# Sheet1.net
KiCad netlist of a schematic drawn in Altium Designer
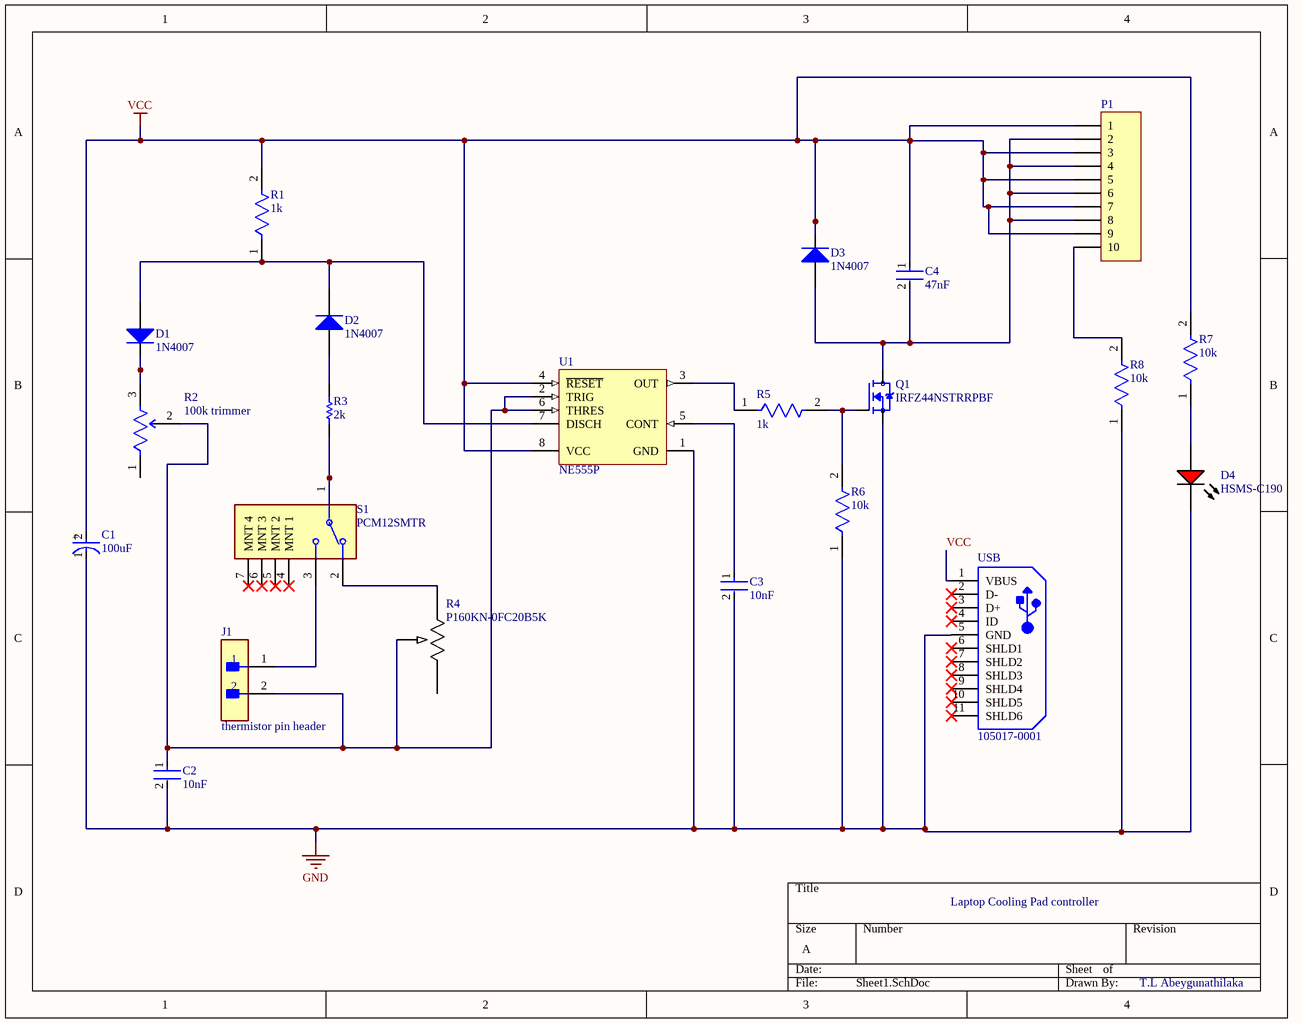
[diagram p0: Sheet1.SchDoc]

(export (version "E")
  (design (tool "Eeschema 10.0.6"))
  (components
    (comp (ref "C1")
      (value "100uF")
      (footprint "FP-TAJW-MFG")
      (description "100uF 4V  ±10% 400mΩ 2312  SMD Tantalum Capacitor")
      (fields (field (name "TOLERANCE") "10%"))
      (libsource (lib "Altium Content Vault") (part "a00bbbee19879c290e62620ae7e47b1"))
    )
    (comp (ref "C2")
      (value "10nF")
      (footprint "FP-0805-L_2_01_0_2-W_1_25-IPC_B")
      (description "General Purpose Ceramic Capacitor, 0805, 10nF, 5%, X7R, 0.15, 50V")
      (fields (field (name "VOLTAGE") "50V") (field (name "TOLERANCE") "5%"))
      (libsource (lib "Altium Content Vault") (part "02cd4be3c70576c341d710602a673aa"))
    )
    (comp (ref "C3")
      (value "10nF")
      (footprint "FP-0805-L_2_01_0_2-W_1_25-IPC_B")
      (description "General Purpose Ceramic Capacitor, 0805, 10nF, 5%, X7R, 0.15, 50V")
      (fields (field (name "VOLTAGE") "50V") (field (name "TOLERANCE") "5%"))
      (libsource (lib "Altium Content Vault") (part "02cd4be3c70576c341d710602a673aa"))
    )
    (comp (ref "C4")
      (value "47nF")
      (footprint "FP-VY2472M49Y5UG63V7-MFG")
      (description "Capacitor Ceramic 4700pF ±20% Y5U BULK RADIAL")
      (fields (field (name "TOLERANCE") "20%"))
      (libsource (lib "Altium Content Vault") (part "02cd4be3c70576c341d710602a673aa"))
    )
    (comp (ref "D1")
      (value "1N4007")
      (footprint "My_DO41")
      (description "1 Amp Diode")
      (fields (field (name "ASID PART NUMBER") "1n4007-AS"))
      (libsource (lib "Mylib+Rev+4") (part "1N4007"))
    )
    (comp (ref "D2")
      (value "1N4007")
      (footprint "My_DO41")
      (description "1 Amp Diode")
      (fields (field (name "ASID PART NUMBER") "1n4007-AS"))
      (libsource (lib "Mylib+Rev+4") (part "1N4007"))
    )
    (comp (ref "D3")
      (value "1N4007")
      (footprint "My_DO41")
      (description "1 Amp Diode")
      (fields (field (name "ASID PART NUMBER") "1n4007-AS"))
      (libsource (lib "Mylib+Rev+4") (part "1N4007"))
    )
    (comp (ref "D4")
      (value "HSMS-C190")
      (footprint "AVAG-HSMX-C190_V")
      (description "LED Uni-Color Red, 52 mW, 20 mA, -40 to 85 degC, 2-Pin SMD, RoHS, Tape and Reel")
      (fields (field (name "MANUFACTURER") "Avago"))
      (libsource (lib "Altium Content Vault") (part "LED-RED-AK-2"))
    )
    (comp (ref "J1")
      (value "thermistor pin header")
      (footprint "FP-M22-2510205-MFG")
      (description "CONN HEADER VERT 2POS 2MM")
      (fields
        (field (name "MANUFACTURER") "Harwin")
        (field (name "OCTOPART") "https://octopart.com/m22-2510205-harwin-2538221")
      )
      (libsource (lib "Altium Content Vault") (part "3bc925449376181038e59eaffc5286c"))
    )
    (comp (ref "P1")
      (value "Header 10")
      (footprint "MY_MA10-1")
      (description "Header, 10-Pin")
      (fields (field (name "ASID PART NUMBER") "Header 10-AS"))
      (libsource (lib "Mylib+Rev+4") (part "Header 10"))
    )
    (comp (ref "Q1")
      (value "IRFZ44NSTRRPBF")
      (footprint "DPAK254P1524X483-3N")
      (fields (field (name "MF") "Infineon Technologies"))
      (libsource (lib "IRFZ44NSTRRPBF") (part "IRFZ44NSTRRPBF"))
    )
    (comp (ref "R1")
      (value "1k")
      (footprint "FP-RP732B-MFG")
      (description "Res Thin Film 1206 1.0KΩ 0.1% 0.25W 15ppm/°C Molded SMD")
      (fields
        (field (name "OCTOPART") "https://octopart.com/rp73d2b1k0btg-te+connectivity-42012461")
        (field (name "MANUFACTURER") "TE Connectivity")
      )
      (libsource (lib "Altium Content Vault") (part "1029c3af85768c4190bb7ad29bc67b5"))
    )
    (comp (ref "R2")
      (value "100k trimmer")
      (footprint "FP-3296W-MFG")
      (description "TRIMMER 50K OHM 0.5W PC PIN TOP")
      (fields (field (name "TOLERANCE") "10%"))
      (libsource (lib "Altium Content Vault") (part "2dcfd2547301a7d3209a5e99acfd772"))
    )
    (comp (ref "R3")
      (value "2k")
      (footprint "RESC2013X60X35LL10T20")
      (fields (field (name "PART NUMBER") "RT0805FRE072KL") (field (name "MANUFACTURER") "Yageo"))
      (libsource (lib "Altium Content Vault") (part "RES"))
    )
    (comp (ref "R4")
      (value "P160KN-0FC20B5K")
      (footprint "POT_P160KN_F20_TTE")
      (description "No Description Available")
      (libsource (lib "P160KN-0FC20B5K") (part "P160KN-0FC20B5K"))
    )
    (comp (ref "R5")
      (value "1k")
      (footprint "FP-RC2012-MFG")
      (description "Res Thick Film 0805 1kΩ 1% 0.125W ±100ppm/°C Molded SMD T/R")
      (fields (field (name "TOLERANCE") "1%"))
      (libsource (lib "Altium Content Vault") (part "1029c3af85768c4190bb7ad29bc67b5"))
    )
    (comp (ref "R6")
      (value "10k")
      (footprint "FP-RMCF0805-IPC_A")
      (description "10kΩ ±5% 0.125W 0805 Thick Film Chip Resistor AEC-Q200 compliant")
      (fields (field (name "TOLERANCE") "5%"))
      (libsource (lib "Altium Content Vault") (part "1029c3af85768c4190bb7ad29bc67b5"))
    )
    (comp (ref "R7")
      (value "10k")
      (footprint "FP-RMCF0805-IPC_A")
      (description "10kΩ ±5% 0.125W 0805 Thick Film Chip Resistor AEC-Q200 compliant")
      (fields (field (name "TOLERANCE") "5%"))
      (libsource (lib "Altium Content Vault") (part "1029c3af85768c4190bb7ad29bc67b5"))
    )
    (comp (ref "R8")
      (value "10k")
      (footprint "FP-RMCF0805-IPC_A")
      (description "10kΩ ±5% 0.125W 0805 Thick Film Chip Resistor AEC-Q200 compliant")
      (fields (field (name "TOLERANCE") "5%"))
      (libsource (lib "Altium Content Vault") (part "1029c3af85768c4190bb7ad29bc67b5"))
    )
    (comp (ref "S1")
      (value "PCM12SMTR")
      (footprint "FP-PCM12SMTR-MFG")
      (description "SWITCH SLIDE SPDT 300MA 6V")
      (libsource (lib "Altium Content Vault") (part "1a3f67d7e2b5469b171eeab59ffb4d2"))
    )
    (comp (ref "U1")
      (value "NE555P")
      (footprint "P0008A")
      (description "Precision Timer, 4.5 to 16 V, 0 to 70 degC, 8-Pin DIP, Pb-Free, Tube")
      (fields (field (name "MANUFACTURER") "TexasInstruments"))
      (libsource (lib "Altium Content Vault") (part "TI-NE555-P8"))
    )
    (comp (ref "USB")
      (value "105017-0001")
      (footprint "USB-MICRO-B_V")
      (fields (field (name "MANUFACTURER") "Molex"))
      (libsource (lib "Altium Content Vault") (part "USB-5-6SHLD"))
    )
  )
  (nets
    (net (code "1") (name "GND") (class "Default")
      (node (ref "C1") (pin "1") (pinfunction "C_1") (pintype "passive"))
      (node (ref "C2") (pin "2") (pinfunction "2_2") (pintype "passive"))
      (node (ref "C3") (pin "2") (pinfunction "2_2") (pintype "passive"))
      (node (ref "D4") (pin "2") (pinfunction "K_2") (pintype "passive"))
      (node (ref "Q1") (pin "3") (pinfunction "S_3") (pintype "passive"))
      (node (ref "R6") (pin "1") (pinfunction "1_1") (pintype "passive"))
      (node (ref "R8") (pin "1") (pinfunction "1_1") (pintype "passive"))
      (node (ref "U1") (pin "1") (pinfunction "GND_1") (pintype "power_in"))
      (node (ref "USB") (pin "5") (pinfunction "GND_5") (pintype "passive"))
    )
    (net (code "2") (name "Net-(D2-PadA)") (class "Default")
      (node (ref "D2") (pin "A") (pinfunction "A_A") (pintype "passive"))
      (node (ref "R3") (pin "2") (pinfunction "2_2") (pintype "passive"))
    )
    (net (code "3") (name "Net-(D4-A)") (class "Default")
      (node (ref "D4") (pin "1") (pinfunction "A_1") (pintype "passive"))
      (node (ref "R7") (pin "1") (pinfunction "1_1") (pintype "passive"))
    )
    (net (code "4") (name "Net-(J1-Pad1)") (class "Default")
      (node (ref "J1") (pin "1") (pinfunction "1_1") (pintype "passive"))
      (node (ref "S1") (pin "3") (pinfunction "3_3") (pintype "passive"))
    )
    (net (code "5") (name "Net-(P1-Pad10)") (class "Default")
      (node (ref "P1") (pin "10") (pinfunction "10_10") (pintype "passive"))
      (node (ref "R8") (pin "2") (pinfunction "2_2") (pintype "passive"))
    )
    (net (code "6") (name "Net-(Q1-D)") (class "Default")
      (node (ref "C4") (pin "2") (pinfunction "2_2") (pintype "passive"))
      (node (ref "D3") (pin "A") (pinfunction "A_A") (pintype "passive"))
      (node (ref "P1") (pin "2") (pinfunction "2_2") (pintype "passive"))
      (node (ref "P1") (pin "4") (pinfunction "4_4") (pintype "passive"))
      (node (ref "P1") (pin "6") (pinfunction "6_6") (pintype "passive"))
      (node (ref "P1") (pin "8") (pinfunction "8_8") (pintype "passive"))
      (node (ref "Q1") (pin "2") (pinfunction "D_2") (pintype "passive"))
    )
    (net (code "7") (name "Net-(Q1-G)") (class "Default")
      (node (ref "Q1") (pin "1") (pinfunction "G_1") (pintype "passive"))
      (node (ref "R5") (pin "2") (pinfunction "2_2") (pintype "passive"))
      (node (ref "R6") (pin "2") (pinfunction "2_2") (pintype "passive"))
    )
    (net (code "8") (name "Net-(R2-CW)") (class "Default")
      (node (ref "D1") (pin "K") (pinfunction "K_K") (pintype "passive"))
      (node (ref "R2") (pin "3") (pinfunction "CW_3") (pintype "passive"))
    )
    (net (code "9") (name "Net-(R2-WIPER)") (class "Default")
      (node (ref "C2") (pin "1") (pinfunction "1_1") (pintype "passive"))
      (node (ref "J1") (pin "2") (pinfunction "2_2") (pintype "passive"))
      (node (ref "R2") (pin "2") (pinfunction "WIPER_2") (pintype "passive"))
      (node (ref "R4") (pin "2") (pinfunction "2_2") (pintype "passive"))
      (node (ref "U1") (pin "2") (pinfunction "TRIG_2") (pintype "input"))
      (node (ref "U1") (pin "6") (pinfunction "THRES_6") (pintype "input"))
    )
    (net (code "10") (name "Net-(R3-Pad1)") (class "Default")
      (node (ref "R3") (pin "1") (pinfunction "1_1") (pintype "passive"))
      (node (ref "S1") (pin "1") (pinfunction "1_1") (pintype "passive"))
    )
    (net (code "11") (name "Net-(R4-Pad3)") (class "Default")
      (node (ref "R4") (pin "3") (pinfunction "3_3") (pintype "passive"))
      (node (ref "S1") (pin "2") (pinfunction "2_2") (pintype "passive"))
    )
    (net (code "12") (name "Net-(U1-CONT)") (class "Default")
      (node (ref "C3") (pin "1") (pinfunction "1_1") (pintype "passive"))
      (node (ref "U1") (pin "5") (pinfunction "CONT_5") (pintype "input"))
    )
    (net (code "13") (name "Net-(U1-DISCH)") (class "Default")
      (node (ref "D1") (pin "A") (pinfunction "A_A") (pintype "passive"))
      (node (ref "D2") (pin "K") (pinfunction "K_K") (pintype "passive"))
      (node (ref "R1") (pin "1") (pinfunction "1_1") (pintype "passive"))
      (node (ref "U1") (pin "7") (pinfunction "DISCH_7") (pintype "open_collector"))
    )
    (net (code "14") (name "Net-(U1-OUT)") (class "Default")
      (node (ref "R5") (pin "1") (pinfunction "1_1") (pintype "passive"))
      (node (ref "U1") (pin "3") (pinfunction "OUT_3") (pintype "output"))
    )
    (net (code "15") (name "VCC") (class "Default")
      (node (ref "C1") (pin "2") (pinfunction "A_2") (pintype "passive"))
      (node (ref "C4") (pin "1") (pinfunction "1_1") (pintype "passive"))
      (node (ref "D3") (pin "K") (pinfunction "K_K") (pintype "passive"))
      (node (ref "P1") (pin "1") (pinfunction "1_1") (pintype "passive"))
      (node (ref "P1") (pin "3") (pinfunction "3_3") (pintype "passive"))
      (node (ref "P1") (pin "5") (pinfunction "5_5") (pintype "passive"))
      (node (ref "P1") (pin "7") (pinfunction "7_7") (pintype "passive"))
      (node (ref "P1") (pin "9") (pinfunction "9_9") (pintype "passive"))
      (node (ref "R1") (pin "2") (pinfunction "2_2") (pintype "passive"))
      (node (ref "R7") (pin "2") (pinfunction "2_2") (pintype "passive"))
      (node (ref "U1") (pin "4") (pinfunction "~{RESET}_4") (pintype "input"))
      (node (ref "U1") (pin "8") (pinfunction "VCC_8") (pintype "power_in"))
      (node (ref "USB") (pin "1") (pinfunction "VBUS_1") (pintype "passive"))
    )
    (net (code "16") (name "unconnected-(R2-CCW-Pad1)") (class "Default")
      (node (ref "R2") (pin "1") (pinfunction "CCW_1") (pintype "passive"))
    )
    (net (code "17") (name "unconnected-(R4-Pad1)") (class "Default")
      (node (ref "R4") (pin "1") (pinfunction "1_1") (pintype "passive"))
    )
    (net (code "18") (name "unconnected-(S1-MNT_1-Pad4)") (class "Default")
      (node (ref "S1") (pin "4") (pinfunction "MNT_1_4") (pintype "passive+no_connect"))
    )
    (net (code "19") (name "unconnected-(S1-MNT_2-Pad5)") (class "Default")
      (node (ref "S1") (pin "5") (pinfunction "MNT_2_5") (pintype "passive+no_connect"))
    )
    (net (code "20") (name "unconnected-(S1-MNT_3-Pad6)") (class "Default")
      (node (ref "S1") (pin "6") (pinfunction "MNT_3_6") (pintype "passive+no_connect"))
    )
    (net (code "21") (name "unconnected-(S1-MNT_4-Pad7)") (class "Default")
      (node (ref "S1") (pin "7") (pinfunction "MNT_4_7") (pintype "passive+no_connect"))
    )
    (net (code "22") (name "unconnected-(USB-D+-Pad3)") (class "Default")
      (node (ref "USB") (pin "3") (pinfunction "D+_3") (pintype "passive+no_connect"))
    )
    (net (code "23") (name "unconnected-(USB-D--Pad2)") (class "Default")
      (node (ref "USB") (pin "2") (pinfunction "D-_2") (pintype "passive+no_connect"))
    )
    (net (code "24") (name "unconnected-(USB-ID-Pad4)") (class "Default")
      (node (ref "USB") (pin "4") (pinfunction "ID_4") (pintype "passive+no_connect"))
    )
    (net (code "25") (name "unconnected-(USB-SHLD1-Pad6)") (class "Default")
      (node (ref "USB") (pin "6") (pinfunction "SHLD1_6") (pintype "passive+no_connect"))
    )
    (net (code "26") (name "unconnected-(USB-SHLD2-Pad7)") (class "Default")
      (node (ref "USB") (pin "7") (pinfunction "SHLD2_7") (pintype "passive+no_connect"))
    )
    (net (code "27") (name "unconnected-(USB-SHLD3-Pad8)") (class "Default")
      (node (ref "USB") (pin "8") (pinfunction "SHLD3_8") (pintype "passive+no_connect"))
    )
    (net (code "28") (name "unconnected-(USB-SHLD4-Pad9)") (class "Default")
      (node (ref "USB") (pin "9") (pinfunction "SHLD4_9") (pintype "passive+no_connect"))
    )
    (net (code "29") (name "unconnected-(USB-SHLD5-Pad10)") (class "Default")
      (node (ref "USB") (pin "10") (pinfunction "SHLD5_10") (pintype "passive+no_connect"))
    )
    (net (code "30") (name "unconnected-(USB-SHLD6-Pad11)") (class "Default")
      (node (ref "USB") (pin "11") (pinfunction "SHLD6_11") (pintype "passive+no_connect"))
    )
  )
)
